# CurrentStabilizer_VER3.net
KiCad netlist of a schematic drawn in EAGLE
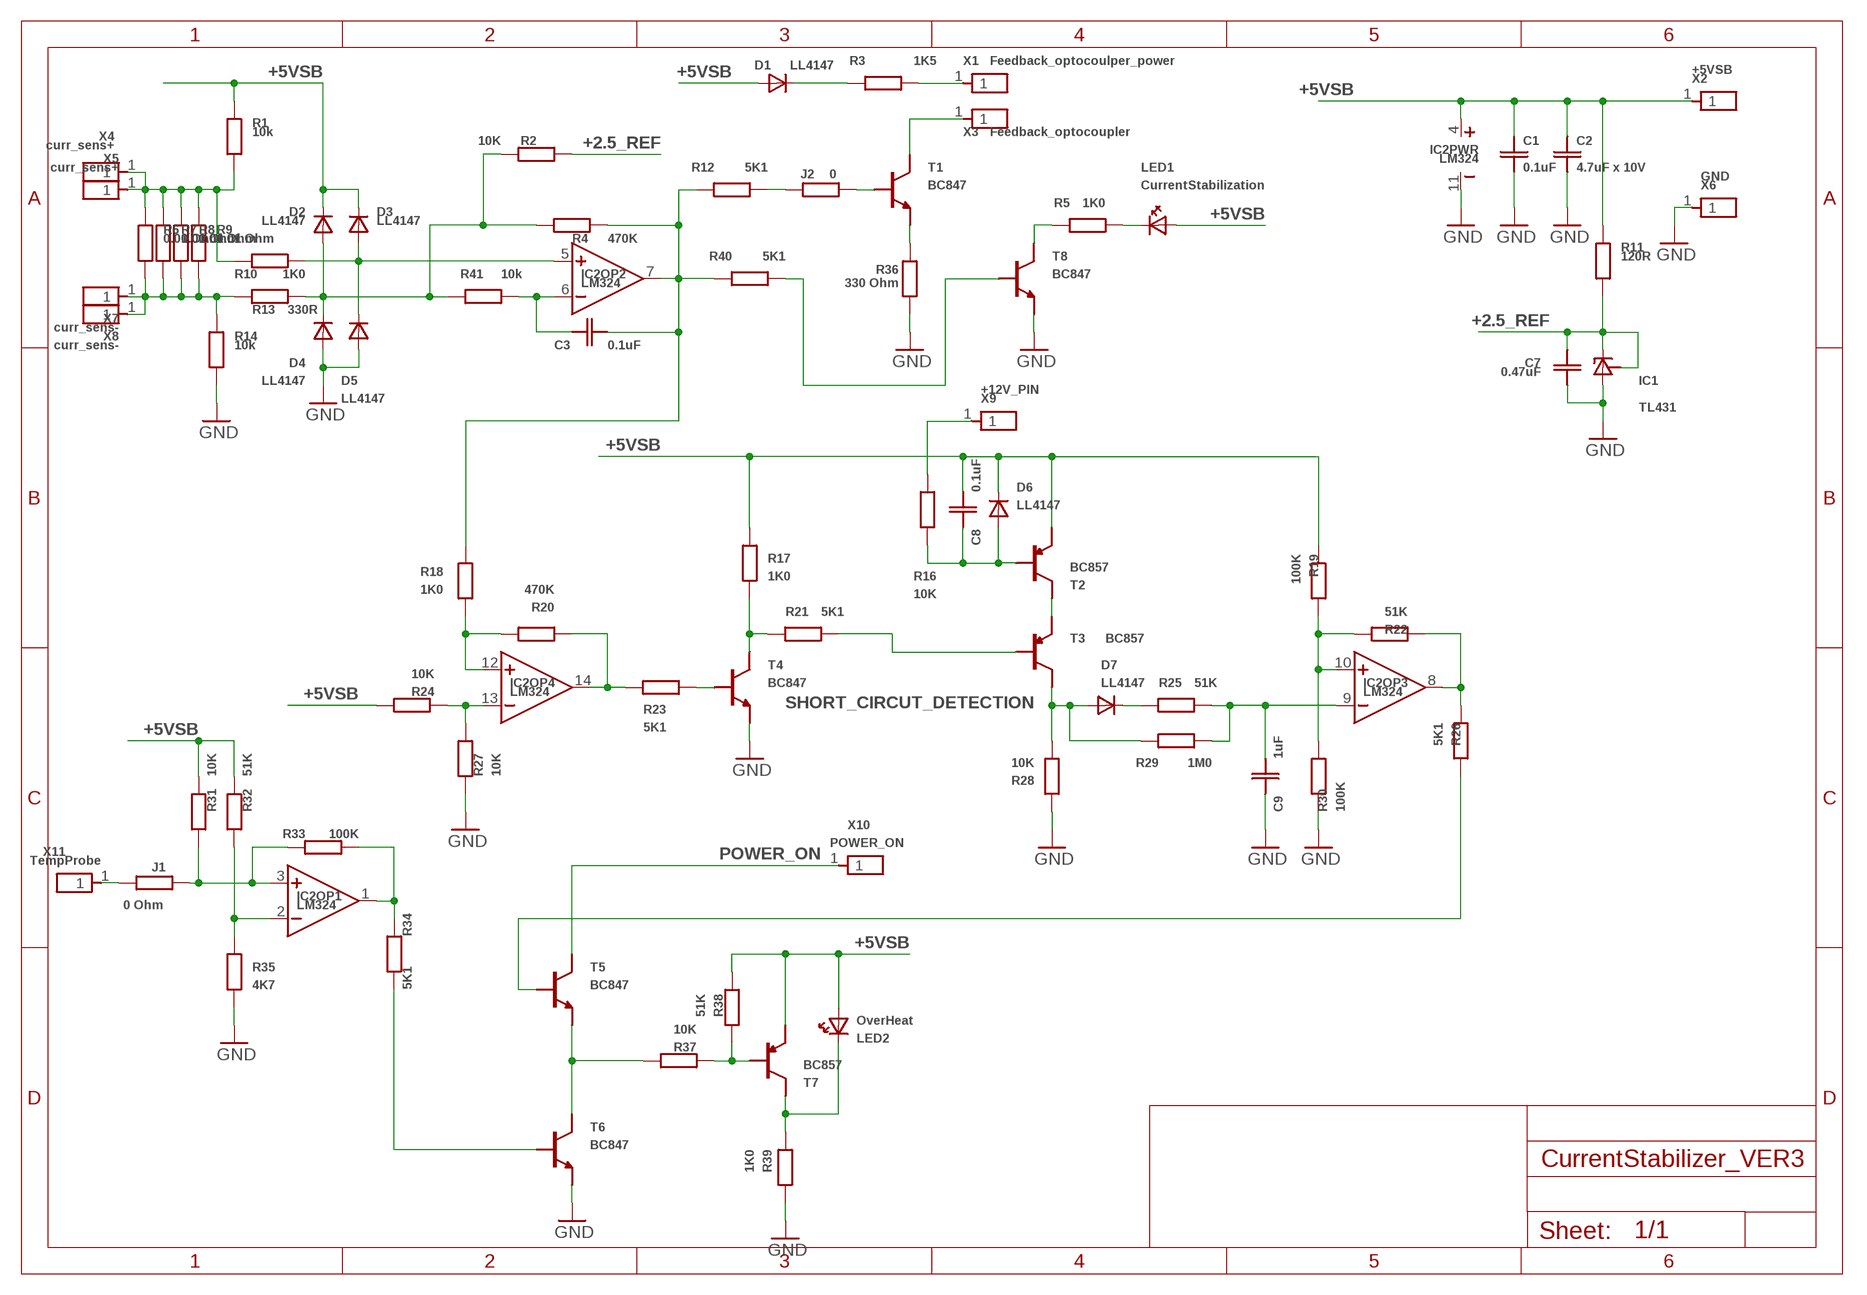
[diagram p0: schematic, sheet 1]

(export (version "E")
  (design (tool "Eeschema 10.0.6"))
  (components
    (comp (ref "C1")
      (value "0.1uF")
      (footprint "eagle-import:RSMD_0805")
      (libsource (lib "eagle-import") (part "CSMD_0805"))
    )
    (comp (ref "C2")
      (value "4.7uF x 10V")
      (footprint "eagle-import:RSMD_1206")
      (libsource (lib "eagle-import") (part "CSMD_1206"))
    )
    (comp (ref "C3")
      (value "0.1uF")
      (footprint "eagle-import:RSMD_0805")
      (libsource (lib "eagle-import") (part "CSMD_0805"))
    )
    (comp (ref "C7")
      (value "0.47uF")
      (footprint "eagle-import:RSMD_0805")
      (libsource (lib "eagle-import") (part "CSMD_0805"))
    )
    (comp (ref "C8")
      (value "0.1uF")
      (footprint "eagle-import:RSMD_0805")
      (libsource (lib "eagle-import") (part "CSMD_0805"))
    )
    (comp (ref "C9")
      (value "1uF")
      (footprint "eagle-import:RSMD_0805")
      (libsource (lib "eagle-import") (part "CSMD_0805"))
    )
    (comp (ref "D1")
      (value "LL4147")
      (footprint "eagle-import:SOD-80")
      (libsource (lib "eagle-import") (part "LL4147SOD-80"))
    )
    (comp (ref "D2")
      (value "LL4147")
      (footprint "eagle-import:SOD-80")
      (libsource (lib "eagle-import") (part "LL4147SOD-80"))
    )
    (comp (ref "D3")
      (value "LL4147")
      (footprint "eagle-import:SOD-80")
      (libsource (lib "eagle-import") (part "LL4147SOD-80"))
    )
    (comp (ref "D4")
      (value "LL4147")
      (footprint "eagle-import:SOD-80")
      (libsource (lib "eagle-import") (part "LL4147SOD-80"))
    )
    (comp (ref "D5")
      (value "LL4147")
      (footprint "eagle-import:SOD-80")
      (libsource (lib "eagle-import") (part "LL4147SOD-80"))
    )
    (comp (ref "D6")
      (value "LL4147")
      (footprint "eagle-import:SOD-80")
      (libsource (lib "eagle-import") (part "LL4147SOD-80"))
    )
    (comp (ref "D7")
      (value "LL4147")
      (footprint "eagle-import:SOD-80")
      (libsource (lib "eagle-import") (part "LL4147SOD-80"))
    )
    (comp (ref "IC1")
      (value "TL431")
      (footprint "eagle-import:SOT23")
      (libsource (lib "eagle-import") (part "TL431SOT23"))
    )
    (comp (ref "IC2")
      (value "LM324")
      (footprint "eagle-import:SOIC14")
      (libsource (lib "eagle-import") (part "LM324"))
    )
    (comp (ref "J1")
      (value "0 Ohm")
      (footprint "eagle-import:RSMD_0805")
      (libsource (lib "eagle-import") (part "RSMD_0805"))
    )
    (comp (ref "J2")
      (value "0")
      (footprint "eagle-import:RSMD_0805")
      (libsource (lib "eagle-import") (part "RSMD_0805"))
    )
    (comp (ref "LED1")
      (value "CurrentStabilization")
      (footprint "eagle-import:LED3MM")
      (libsource (lib "eagle-import") (part "LED3MM"))
    )
    (comp (ref "LED2")
      (value "OverHeat")
      (footprint "eagle-import:LED3MM")
      (libsource (lib "eagle-import") (part "LED3MM"))
    )
    (comp (ref "R1")
      (value "10k")
      (footprint "eagle-import:RSMD_0805")
      (libsource (lib "eagle-import") (part "RSMD_0805"))
    )
    (comp (ref "R2")
      (value "10K")
      (footprint "eagle-import:RSMD_0805")
      (libsource (lib "eagle-import") (part "RSMD_0805"))
    )
    (comp (ref "R3")
      (value "1K5")
      (footprint "eagle-import:RSMD_0805")
      (libsource (lib "eagle-import") (part "RSMD_0805"))
    )
    (comp (ref "R4")
      (value "470K")
      (footprint "eagle-import:RSMD_0805")
      (libsource (lib "eagle-import") (part "RSMD_0805"))
    )
    (comp (ref "R5")
      (value "1K0")
      (footprint "eagle-import:RSMD_0805")
      (libsource (lib "eagle-import") (part "RSMD_0805"))
    )
    (comp (ref "R6")
      (value "0.01 Ohm")
      (footprint "eagle-import:RSMD_2512")
      (libsource (lib "eagle-import") (part "RSMD_2512"))
    )
    (comp (ref "R7")
      (value "0.01 Ohm")
      (footprint "eagle-import:RSMD_2512")
      (libsource (lib "eagle-import") (part "RSMD_2512"))
    )
    (comp (ref "R8")
      (value "0.01 Ohm")
      (footprint "eagle-import:RSMD_2512")
      (libsource (lib "eagle-import") (part "RSMD_2512"))
    )
    (comp (ref "R9")
      (value "0.01 Ohm")
      (footprint "eagle-import:RSMD_2512")
      (libsource (lib "eagle-import") (part "RSMD_2512"))
    )
    (comp (ref "R10")
      (value "1K0")
      (footprint "eagle-import:RSMD_0805")
      (libsource (lib "eagle-import") (part "RSMD_0805"))
    )
    (comp (ref "R11")
      (value "120R")
      (footprint "eagle-import:RSMD_0805")
      (libsource (lib "eagle-import") (part "RSMD_0805"))
    )
    (comp (ref "R12")
      (value "5K1")
      (footprint "eagle-import:RSMD_0805")
      (libsource (lib "eagle-import") (part "RSMD_0805"))
    )
    (comp (ref "R13")
      (value "330R")
      (footprint "eagle-import:RSMD_0805")
      (libsource (lib "eagle-import") (part "RSMD_0805"))
    )
    (comp (ref "R14")
      (value "10k")
      (footprint "eagle-import:RSMD_0805")
      (libsource (lib "eagle-import") (part "RSMD_0805"))
    )
    (comp (ref "R16")
      (value "10K")
      (footprint "eagle-import:RSMD_0805")
      (libsource (lib "eagle-import") (part "RSMD_0805"))
    )
    (comp (ref "R17")
      (value "1K0")
      (footprint "eagle-import:RSMD_0805")
      (libsource (lib "eagle-import") (part "RSMD_0805"))
    )
    (comp (ref "R18")
      (value "1K0")
      (footprint "eagle-import:RSMD_0805")
      (libsource (lib "eagle-import") (part "RSMD_0805"))
    )
    (comp (ref "R19")
      (value "100K")
      (footprint "eagle-import:RSMD_1206_BIG_GAP")
      (libsource (lib "eagle-import") (part "RSMD_1206_BIG_GAP"))
    )
    (comp (ref "R20")
      (value "470K")
      (footprint "eagle-import:RSMD_0805")
      (libsource (lib "eagle-import") (part "RSMD_0805"))
    )
    (comp (ref "R21")
      (value "5K1")
      (footprint "eagle-import:RSMD_0805")
      (libsource (lib "eagle-import") (part "RSMD_0805"))
    )
    (comp (ref "R22")
      (value "51K")
      (footprint "eagle-import:RSMD_0805")
      (libsource (lib "eagle-import") (part "RSMD_0805"))
    )
    (comp (ref "R23")
      (value "5K1")
      (footprint "eagle-import:RSMD_1206_BIG_GAP")
      (libsource (lib "eagle-import") (part "RSMD_1206_BIG_GAP"))
    )
    (comp (ref "R24")
      (value "10K")
      (footprint "eagle-import:RSMD_0805")
      (libsource (lib "eagle-import") (part "RSMD_0805"))
    )
    (comp (ref "R25")
      (value "51K")
      (footprint "eagle-import:RSMD_0805")
      (libsource (lib "eagle-import") (part "RSMD_0805"))
    )
    (comp (ref "R26")
      (value "5K1")
      (footprint "eagle-import:RSMD_0805")
      (libsource (lib "eagle-import") (part "RSMD_0805"))
    )
    (comp (ref "R27")
      (value "10K")
      (footprint "eagle-import:RSMD_0805")
      (libsource (lib "eagle-import") (part "RSMD_0805"))
    )
    (comp (ref "R28")
      (value "10K")
      (footprint "eagle-import:RSMD_0805")
      (libsource (lib "eagle-import") (part "RSMD_0805"))
    )
    (comp (ref "R29")
      (value "1M0")
      (footprint "eagle-import:RSMD_0805")
      (libsource (lib "eagle-import") (part "RSMD_0805"))
    )
    (comp (ref "R30")
      (value "100K")
      (footprint "eagle-import:RSMD_0805")
      (libsource (lib "eagle-import") (part "RSMD_0805"))
    )
    (comp (ref "R31")
      (value "10K")
      (footprint "eagle-import:RSMD_0805")
      (libsource (lib "eagle-import") (part "RSMD_0805"))
    )
    (comp (ref "R32")
      (value "51K")
      (footprint "eagle-import:RSMD_0805")
      (libsource (lib "eagle-import") (part "RSMD_0805"))
    )
    (comp (ref "R33")
      (value "100K")
      (footprint "eagle-import:RSMD_0805")
      (libsource (lib "eagle-import") (part "RSMD_0805"))
    )
    (comp (ref "R34")
      (value "5K1")
      (footprint "eagle-import:RSMD_0805")
      (libsource (lib "eagle-import") (part "RSMD_0805"))
    )
    (comp (ref "R35")
      (value "4K7")
      (footprint "eagle-import:RSMD_0805")
      (libsource (lib "eagle-import") (part "RSMD_0805"))
    )
    (comp (ref "R36")
      (value "330 Ohm")
      (footprint "eagle-import:RSMD_0805")
      (libsource (lib "eagle-import") (part "RSMD_0805"))
    )
    (comp (ref "R37")
      (value "10K")
      (footprint "eagle-import:RSMD_1206_BIG_GAP")
      (libsource (lib "eagle-import") (part "RSMD_1206_BIG_GAP"))
    )
    (comp (ref "R38")
      (value "51K")
      (footprint "eagle-import:RSMD_0805")
      (libsource (lib "eagle-import") (part "RSMD_0805"))
    )
    (comp (ref "R39")
      (value "1K0")
      (footprint "eagle-import:RSMD_0805")
      (libsource (lib "eagle-import") (part "RSMD_0805"))
    )
    (comp (ref "R40")
      (value "5K1")
      (footprint "eagle-import:RSMD_0805")
      (libsource (lib "eagle-import") (part "RSMD_0805"))
    )
    (comp (ref "R41")
      (value "10k")
      (footprint "eagle-import:RSMD_0805")
      (libsource (lib "eagle-import") (part "RSMD_0805"))
    )
    (comp (ref "T1")
      (value "BC847")
      (footprint "eagle-import:SOT23_SMALL_PADS")
      (libsource (lib "eagle-import") (part "BC847SOT23_SMALL_PADS"))
    )
    (comp (ref "T2")
      (value "BC857")
      (footprint "eagle-import:SOT23_SMALL_PADS")
      (libsource (lib "eagle-import") (part "BC857SOT23_SMALL_PADS"))
    )
    (comp (ref "T3")
      (value "BC857")
      (footprint "eagle-import:SOT23_SMALL_PADS")
      (libsource (lib "eagle-import") (part "BC857SOT23_SMALL_PADS"))
    )
    (comp (ref "T4")
      (value "BC847")
      (footprint "eagle-import:SOT23_SMALL_PADS")
      (libsource (lib "eagle-import") (part "BC847SOT23_SMALL_PADS"))
    )
    (comp (ref "T5")
      (value "BC847")
      (footprint "eagle-import:SOT23_SMALL_PADS")
      (libsource (lib "eagle-import") (part "BC847SOT23_SMALL_PADS"))
    )
    (comp (ref "T6")
      (value "BC847")
      (footprint "eagle-import:SOT23_SMALL_PADS")
      (libsource (lib "eagle-import") (part "BC847SOT23_SMALL_PADS"))
    )
    (comp (ref "T7")
      (value "BC857")
      (footprint "eagle-import:SOT23_SMALL_PADS")
      (libsource (lib "eagle-import") (part "BC857SOT23_SMALL_PADS"))
    )
    (comp (ref "T8")
      (value "BC847")
      (footprint "eagle-import:SOT23_SMALL_PADS")
      (libsource (lib "eagle-import") (part "BC847SOT23_SMALL_PADS"))
    )
    (comp (ref "X1")
      (value "Feedback_optocoulper_power")
      (footprint "eagle-import:PIN1X1_2.54MM")
      (libsource (lib "eagle-import") (part "PIN1X12.54MM"))
    )
    (comp (ref "X2")
      (value "+5VSB")
      (footprint "eagle-import:PIN1X1_2.54MM")
      (libsource (lib "eagle-import") (part "PIN1X12.54MM"))
    )
    (comp (ref "X3")
      (value "Feedback_optocoupler")
      (footprint "eagle-import:PIN1X1_2.54MM")
      (libsource (lib "eagle-import") (part "PIN1X12.54MM"))
    )
    (comp (ref "X4")
      (value "curr_sens+")
      (footprint "eagle-import:PIN1X1_2.54MM")
      (libsource (lib "eagle-import") (part "PIN1X12.54MM"))
    )
    (comp (ref "X5")
      (value "curr_sens+")
      (footprint "eagle-import:PIN1X1_2.54MM")
      (libsource (lib "eagle-import") (part "PIN1X12.54MM"))
    )
    (comp (ref "X6")
      (value "GND")
      (footprint "eagle-import:PIN1X1_2.54MM")
      (libsource (lib "eagle-import") (part "PIN1X12.54MM"))
    )
    (comp (ref "X7")
      (value "curr_sens-")
      (footprint "eagle-import:PIN1X1_2.54MM")
      (libsource (lib "eagle-import") (part "PIN1X12.54MM"))
    )
    (comp (ref "X8")
      (value "curr_sens-")
      (footprint "eagle-import:PIN1X1_2.54MM")
      (libsource (lib "eagle-import") (part "PIN1X12.54MM"))
    )
    (comp (ref "X9")
      (value "+12V_PIN")
      (footprint "eagle-import:PIN1X1_2.54MM")
      (libsource (lib "eagle-import") (part "PIN1X12.54MM"))
    )
    (comp (ref "X10")
      (value "POWER_ON")
      (footprint "eagle-import:PIN1X1_2.54MM")
      (libsource (lib "eagle-import") (part "PIN1X12.54MM"))
    )
    (comp (ref "X11")
      (value "TempProbe")
      (footprint "eagle-import:PIN1X1_2.54MM")
      (libsource (lib "eagle-import") (part "PIN1X12.54MM"))
    )
  )
  (nets
    (net (code "1") (name "/+2.5_REF") (class "Default")
      (node (ref "C7") (pin "PAD_1") (pinfunction "PIN1_PAD_1") (pintype "bidirectional"))
      (node (ref "IC1") (pin "1") (pinfunction "CATHODE_1") (pintype "passive"))
      (node (ref "IC1") (pin "2") (pinfunction "REFERENCE_2") (pintype "passive"))
      (node (ref "R11") (pin "PAD_0") (pinfunction "PIN0_PAD_0") (pintype "passive"))
      (node (ref "R2") (pin "PAD_0") (pinfunction "PIN0_PAD_0") (pintype "passive"))
    )
    (net (code "2") (name "/+5VSB") (class "Default")
      (node (ref "C1") (pin "PAD_1") (pinfunction "PIN1_PAD_1") (pintype "bidirectional"))
      (node (ref "C2") (pin "PAD_1") (pinfunction "PIN1_PAD_1") (pintype "bidirectional"))
      (node (ref "C8") (pin "PAD_0") (pinfunction "PIN0_PAD_0") (pintype "bidirectional"))
      (node (ref "D1") (pin "ANODE") (pinfunction "ANODE_ANODE") (pintype "passive"))
      (node (ref "D2") (pin "CATHODE") (pinfunction "CATHODE_CATHODE") (pintype "passive"))
      (node (ref "D3") (pin "CATHODE") (pinfunction "CATHODE_CATHODE") (pintype "passive"))
      (node (ref "D6") (pin "CATHODE") (pinfunction "CATHODE_CATHODE") (pintype "passive"))
      (node (ref "IC2") (pin "4") (pinfunction "VCC_4") (pintype "power_in"))
      (node (ref "LED1") (pin "ANODE") (pinfunction "ANODE_ANODE") (pintype "passive"))
      (node (ref "LED2") (pin "ANODE") (pinfunction "ANODE_ANODE") (pintype "passive"))
      (node (ref "R1") (pin "PAD_1") (pinfunction "PIN1_PAD_1") (pintype "passive"))
      (node (ref "R11") (pin "PAD_1") (pinfunction "PIN1_PAD_1") (pintype "passive"))
      (node (ref "R17") (pin "PAD_0") (pinfunction "PIN0_PAD_0") (pintype "passive"))
      (node (ref "R19") (pin "PAD_0") (pinfunction "PIN0_PAD_0") (pintype "passive"))
      (node (ref "R24") (pin "PAD_1") (pinfunction "PIN1_PAD_1") (pintype "passive"))
      (node (ref "R31") (pin "PAD_1") (pinfunction "PIN1_PAD_1") (pintype "passive"))
      (node (ref "R32") (pin "PAD_1") (pinfunction "PIN1_PAD_1") (pintype "passive"))
      (node (ref "R38") (pin "PAD_0") (pinfunction "PIN0_PAD_0") (pintype "passive"))
      (node (ref "T2") (pin "2") (pinfunction "E_2") (pintype "bidirectional"))
      (node (ref "T7") (pin "2") (pinfunction "E_2") (pintype "bidirectional"))
      (node (ref "X2") (pin "1") (pinfunction "1_1") (pintype "bidirectional"))
    )
    (net (code "3") (name "/POWER_ON") (class "Default")
      (node (ref "T5") (pin "3") (pinfunction "C_3") (pintype "bidirectional"))
      (node (ref "X10") (pin "1") (pinfunction "1_1") (pintype "bidirectional"))
    )
    (net (code "4") (name "/SHORT_CIRCUT_DETECTION") (class "Default")
      (node (ref "D7") (pin "ANODE") (pinfunction "ANODE_ANODE") (pintype "passive"))
      (node (ref "R28") (pin "PAD_0") (pinfunction "PIN0_PAD_0") (pintype "passive"))
      (node (ref "R29") (pin "PAD_1") (pinfunction "PIN1_PAD_1") (pintype "passive"))
      (node (ref "T3") (pin "3") (pinfunction "C_3") (pintype "bidirectional"))
    )
    (net (code "5") (name "GND") (class "Default")
      (node (ref "C1") (pin "PAD_0") (pinfunction "PIN0_PAD_0") (pintype "bidirectional"))
      (node (ref "C2") (pin "PAD_0") (pinfunction "PIN0_PAD_0") (pintype "bidirectional"))
      (node (ref "C7") (pin "PAD_0") (pinfunction "PIN0_PAD_0") (pintype "bidirectional"))
      (node (ref "C9") (pin "PAD_1") (pinfunction "PIN1_PAD_1") (pintype "bidirectional"))
      (node (ref "D4") (pin "ANODE") (pinfunction "ANODE_ANODE") (pintype "passive"))
      (node (ref "D5") (pin "ANODE") (pinfunction "ANODE_ANODE") (pintype "passive"))
      (node (ref "IC1") (pin "3") (pinfunction "ANODE_3") (pintype "passive"))
      (node (ref "IC2") (pin "11") (pinfunction "GND_11") (pintype "power_in"))
      (node (ref "R14") (pin "PAD_0") (pinfunction "PIN0_PAD_0") (pintype "passive"))
      (node (ref "R27") (pin "PAD_0") (pinfunction "PIN0_PAD_0") (pintype "passive"))
      (node (ref "R28") (pin "PAD_1") (pinfunction "PIN1_PAD_1") (pintype "passive"))
      (node (ref "R30") (pin "PAD_0") (pinfunction "PIN0_PAD_0") (pintype "passive"))
      (node (ref "R35") (pin "PAD_0") (pinfunction "PIN0_PAD_0") (pintype "passive"))
      (node (ref "R36") (pin "PAD_0") (pinfunction "PIN0_PAD_0") (pintype "passive"))
      (node (ref "R39") (pin "PAD_1") (pinfunction "PIN1_PAD_1") (pintype "passive"))
      (node (ref "T4") (pin "2") (pinfunction "E_2") (pintype "bidirectional"))
      (node (ref "T6") (pin "2") (pinfunction "E_2") (pintype "bidirectional"))
      (node (ref "T8") (pin "2") (pinfunction "E_2") (pintype "bidirectional"))
      (node (ref "X6") (pin "1") (pinfunction "1_1") (pintype "bidirectional"))
    )
    (net (code "6") (name "Net-(C3-PIN0)") (class "Default")
      (node (ref "C3") (pin "PAD_0") (pinfunction "PIN0_PAD_0") (pintype "bidirectional"))
      (node (ref "IC2") (pin "7") (pinfunction "OUT_7") (pintype "output"))
      (node (ref "R12") (pin "PAD_1") (pinfunction "PIN1_PAD_1") (pintype "passive"))
      (node (ref "R18") (pin "PAD_1") (pinfunction "PIN1_PAD_1") (pintype "passive"))
      (node (ref "R4") (pin "PAD_1") (pinfunction "PIN1_PAD_1") (pintype "passive"))
      (node (ref "R40") (pin "PAD_1") (pinfunction "PIN1_PAD_1") (pintype "passive"))
    )
    (net (code "7") (name "Net-(C3-PIN1)") (class "Default")
      (node (ref "C3") (pin "PAD_1") (pinfunction "PIN1_PAD_1") (pintype "bidirectional"))
      (node (ref "IC2") (pin "6") (pinfunction "IN-_6") (pintype "input"))
      (node (ref "R41") (pin "PAD_0") (pinfunction "PIN0_PAD_0") (pintype "passive"))
    )
    (net (code "8") (name "Net-(C8-PIN1)") (class "Default")
      (node (ref "C8") (pin "PAD_1") (pinfunction "PIN1_PAD_1") (pintype "bidirectional"))
      (node (ref "D6") (pin "ANODE") (pinfunction "ANODE_ANODE") (pintype "passive"))
      (node (ref "R16") (pin "PAD_1") (pinfunction "PIN1_PAD_1") (pintype "passive"))
      (node (ref "T2") (pin "1") (pinfunction "B_1") (pintype "bidirectional"))
    )
    (net (code "9") (name "Net-(C9-PIN0)") (class "Default")
      (node (ref "C9") (pin "PAD_0") (pinfunction "PIN0_PAD_0") (pintype "bidirectional"))
      (node (ref "IC2") (pin "9") (pinfunction "IN-_9") (pintype "input"))
      (node (ref "R25") (pin "PAD_1") (pinfunction "PIN1_PAD_1") (pintype "passive"))
      (node (ref "R29") (pin "PAD_0") (pinfunction "PIN0_PAD_0") (pintype "passive"))
    )
    (net (code "10") (name "Net-(IC2A-IN+)") (class "Default")
      (node (ref "IC2") (pin "3") (pinfunction "IN+_3") (pintype "input"))
      (node (ref "J1") (pin "PAD_0") (pinfunction "PIN0_PAD_0") (pintype "passive"))
      (node (ref "R31") (pin "PAD_0") (pinfunction "PIN0_PAD_0") (pintype "passive"))
      (node (ref "R33") (pin "PAD_1") (pinfunction "PIN1_PAD_1") (pintype "passive"))
    )
    (net (code "11") (name "Net-(IC2A-IN-)") (class "Default")
      (node (ref "IC2") (pin "2") (pinfunction "IN-_2") (pintype "input"))
      (node (ref "R32") (pin "PAD_0") (pinfunction "PIN0_PAD_0") (pintype "passive"))
      (node (ref "R35") (pin "PAD_1") (pinfunction "PIN1_PAD_1") (pintype "passive"))
    )
    (net (code "12") (name "Net-(IC2A-OUT)") (class "Default")
      (node (ref "IC2") (pin "1") (pinfunction "OUT_1") (pintype "output"))
      (node (ref "R33") (pin "PAD_0") (pinfunction "PIN0_PAD_0") (pintype "passive"))
      (node (ref "R34") (pin "PAD_1") (pinfunction "PIN1_PAD_1") (pintype "passive"))
    )
    (net (code "13") (name "Net-(IC2B-IN+)") (class "Default")
      (node (ref "D3") (pin "ANODE") (pinfunction "ANODE_ANODE") (pintype "passive"))
      (node (ref "D5") (pin "CATHODE") (pinfunction "CATHODE_CATHODE") (pintype "passive"))
      (node (ref "IC2") (pin "5") (pinfunction "IN+_5") (pintype "input"))
      (node (ref "R10") (pin "PAD_1") (pinfunction "PIN1_PAD_1") (pintype "passive"))
    )
    (net (code "14") (name "Net-(IC2C-IN+)") (class "Default")
      (node (ref "IC2") (pin "10") (pinfunction "IN+_10") (pintype "input"))
      (node (ref "R19") (pin "PAD_1") (pinfunction "PIN1_PAD_1") (pintype "passive"))
      (node (ref "R22") (pin "PAD_1") (pinfunction "PIN1_PAD_1") (pintype "passive"))
      (node (ref "R30") (pin "PAD_1") (pinfunction "PIN1_PAD_1") (pintype "passive"))
    )
    (net (code "15") (name "Net-(IC2C-OUT)") (class "Default")
      (node (ref "IC2") (pin "8") (pinfunction "OUT_8") (pintype "output"))
      (node (ref "R22") (pin "PAD_0") (pinfunction "PIN0_PAD_0") (pintype "passive"))
      (node (ref "R26") (pin "PAD_0") (pinfunction "PIN0_PAD_0") (pintype "passive"))
    )
    (net (code "16") (name "Net-(IC2D-IN+)") (class "Default")
      (node (ref "IC2") (pin "12") (pinfunction "IN+_12") (pintype "input"))
      (node (ref "R18") (pin "PAD_0") (pinfunction "PIN0_PAD_0") (pintype "passive"))
      (node (ref "R20") (pin "PAD_0") (pinfunction "PIN0_PAD_0") (pintype "passive"))
    )
    (net (code "17") (name "Net-(IC2D-IN-)") (class "Default")
      (node (ref "IC2") (pin "13") (pinfunction "IN-_13") (pintype "input"))
      (node (ref "R24") (pin "PAD_0") (pinfunction "PIN0_PAD_0") (pintype "passive"))
      (node (ref "R27") (pin "PAD_1") (pinfunction "PIN1_PAD_1") (pintype "passive"))
    )
    (net (code "18") (name "Net-(IC2D-OUT)") (class "Default")
      (node (ref "IC2") (pin "14") (pinfunction "OUT_14") (pintype "output"))
      (node (ref "R20") (pin "PAD_1") (pinfunction "PIN1_PAD_1") (pintype "passive"))
      (node (ref "R23") (pin "PAD_1") (pinfunction "PIN1_PAD_1") (pintype "passive"))
    )
    (net (code "19") (name "Net-(J1-PIN1)") (class "Default")
      (node (ref "J1") (pin "PAD_1") (pinfunction "PIN1_PAD_1") (pintype "passive"))
      (node (ref "X11") (pin "1") (pinfunction "1_1") (pintype "bidirectional"))
    )
    (net (code "20") (name "Net-(J2-PIN0)") (class "Default")
      (node (ref "J2") (pin "PAD_0") (pinfunction "PIN0_PAD_0") (pintype "passive"))
      (node (ref "T1") (pin "1") (pinfunction "B_1") (pintype "bidirectional"))
    )
    (net (code "21") (name "Net-(J2-PIN1)") (class "Default")
      (node (ref "J2") (pin "PAD_1") (pinfunction "PIN1_PAD_1") (pintype "passive"))
      (node (ref "R12") (pin "PAD_0") (pinfunction "PIN0_PAD_0") (pintype "passive"))
    )
    (net (code "22") (name "Net-(R1-PIN0)") (class "Default")
      (node (ref "R1") (pin "PAD_0") (pinfunction "PIN0_PAD_0") (pintype "passive"))
      (node (ref "R10") (pin "PAD_0") (pinfunction "PIN0_PAD_0") (pintype "passive"))
      (node (ref "R6") (pin "PAD1") (pinfunction "PIN1_PAD1") (pintype "passive"))
      (node (ref "R7") (pin "PAD1") (pinfunction "PIN1_PAD1") (pintype "passive"))
      (node (ref "R8") (pin "PAD1") (pinfunction "PIN1_PAD1") (pintype "passive"))
      (node (ref "R9") (pin "PAD1") (pinfunction "PIN1_PAD1") (pintype "passive"))
      (node (ref "X4") (pin "1") (pinfunction "1_1") (pintype "bidirectional"))
      (node (ref "X5") (pin "1") (pinfunction "1_1") (pintype "bidirectional"))
    )
    (net (code "23") (name "Net-(R3-PIN0)") (class "Default")
      (node (ref "R3") (pin "PAD_0") (pinfunction "PIN0_PAD_0") (pintype "passive"))
      (node (ref "X1") (pin "1") (pinfunction "1_1") (pintype "bidirectional"))
    )
    (net (code "24") (name "Net-(R3-PIN1)") (class "Default")
      (node (ref "D1") (pin "CATHODE") (pinfunction "CATHODE_CATHODE") (pintype "passive"))
      (node (ref "R3") (pin "PAD_1") (pinfunction "PIN1_PAD_1") (pintype "passive"))
    )
    (net (code "25") (name "Net-(R5-PIN0)") (class "Default")
      (node (ref "LED1") (pin "CATHODE") (pinfunction "CATHODE_CATHODE") (pintype "passive"))
      (node (ref "R5") (pin "PAD_0") (pinfunction "PIN0_PAD_0") (pintype "passive"))
    )
    (net (code "26") (name "Net-(R5-PIN1)") (class "Default")
      (node (ref "R5") (pin "PAD_1") (pinfunction "PIN1_PAD_1") (pintype "passive"))
      (node (ref "T8") (pin "3") (pinfunction "C_3") (pintype "bidirectional"))
    )
    (net (code "27") (name "Net-(R13-PIN0)") (class "Default")
      (node (ref "R13") (pin "PAD_0") (pinfunction "PIN0_PAD_0") (pintype "passive"))
      (node (ref "R14") (pin "PAD_1") (pinfunction "PIN1_PAD_1") (pintype "passive"))
      (node (ref "R6") (pin "PAD0") (pinfunction "PIN0_PAD0") (pintype "passive"))
      (node (ref "R7") (pin "PAD0") (pinfunction "PIN0_PAD0") (pintype "passive"))
      (node (ref "R8") (pin "PAD0") (pinfunction "PIN0_PAD0") (pintype "passive"))
      (node (ref "R9") (pin "PAD0") (pinfunction "PIN0_PAD0") (pintype "passive"))
      (node (ref "X7") (pin "1") (pinfunction "1_1") (pintype "bidirectional"))
      (node (ref "X8") (pin "1") (pinfunction "1_1") (pintype "bidirectional"))
    )
    (net (code "28") (name "Net-(R13-PIN1)") (class "Default")
      (node (ref "D2") (pin "ANODE") (pinfunction "ANODE_ANODE") (pintype "passive"))
      (node (ref "D4") (pin "CATHODE") (pinfunction "CATHODE_CATHODE") (pintype "passive"))
      (node (ref "R13") (pin "PAD_1") (pinfunction "PIN1_PAD_1") (pintype "passive"))
      (node (ref "R2") (pin "PAD_1") (pinfunction "PIN1_PAD_1") (pintype "passive"))
      (node (ref "R4") (pin "PAD_0") (pinfunction "PIN0_PAD_0") (pintype "passive"))
      (node (ref "R41") (pin "PAD_1") (pinfunction "PIN1_PAD_1") (pintype "passive"))
    )
    (net (code "29") (name "Net-(R16-PIN0)") (class "Default")
      (node (ref "R16") (pin "PAD_0") (pinfunction "PIN0_PAD_0") (pintype "passive"))
      (node (ref "X9") (pin "1") (pinfunction "1_1") (pintype "bidirectional"))
    )
    (net (code "30") (name "Net-(R17-PIN1)") (class "Default")
      (node (ref "R17") (pin "PAD_1") (pinfunction "PIN1_PAD_1") (pintype "passive"))
      (node (ref "R21") (pin "PAD_0") (pinfunction "PIN0_PAD_0") (pintype "passive"))
      (node (ref "T4") (pin "3") (pinfunction "C_3") (pintype "bidirectional"))
    )
    (net (code "31") (name "Net-(R21-PIN1)") (class "Default")
      (node (ref "R21") (pin "PAD_1") (pinfunction "PIN1_PAD_1") (pintype "passive"))
      (node (ref "T3") (pin "1") (pinfunction "B_1") (pintype "bidirectional"))
    )
    (net (code "32") (name "Net-(R23-PIN0)") (class "Default")
      (node (ref "R23") (pin "PAD_0") (pinfunction "PIN0_PAD_0") (pintype "passive"))
      (node (ref "T4") (pin "1") (pinfunction "B_1") (pintype "bidirectional"))
    )
    (net (code "33") (name "Net-(R25-PIN0)") (class "Default")
      (node (ref "D7") (pin "CATHODE") (pinfunction "CATHODE_CATHODE") (pintype "passive"))
      (node (ref "R25") (pin "PAD_0") (pinfunction "PIN0_PAD_0") (pintype "passive"))
    )
    (net (code "34") (name "Net-(R26-PIN1)") (class "Default")
      (node (ref "R26") (pin "PAD_1") (pinfunction "PIN1_PAD_1") (pintype "passive"))
      (node (ref "T5") (pin "1") (pinfunction "B_1") (pintype "bidirectional"))
    )
    (net (code "35") (name "Net-(R34-PIN0)") (class "Default")
      (node (ref "R34") (pin "PAD_0") (pinfunction "PIN0_PAD_0") (pintype "passive"))
      (node (ref "T6") (pin "1") (pinfunction "B_1") (pintype "bidirectional"))
    )
    (net (code "36") (name "Net-(R36-PIN1)") (class "Default")
      (node (ref "R36") (pin "PAD_1") (pinfunction "PIN1_PAD_1") (pintype "passive"))
      (node (ref "T1") (pin "2") (pinfunction "E_2") (pintype "bidirectional"))
    )
    (net (code "37") (name "Net-(R37-PIN0)") (class "Default")
      (node (ref "R37") (pin "PAD_0") (pinfunction "PIN0_PAD_0") (pintype "passive"))
      (node (ref "R38") (pin "PAD_1") (pinfunction "PIN1_PAD_1") (pintype "passive"))
      (node (ref "T7") (pin "1") (pinfunction "B_1") (pintype "bidirectional"))
    )
    (net (code "38") (name "Net-(R37-PIN1)") (class "Default")
      (node (ref "R37") (pin "PAD_1") (pinfunction "PIN1_PAD_1") (pintype "passive"))
      (node (ref "T5") (pin "2") (pinfunction "E_2") (pintype "bidirectional"))
      (node (ref "T6") (pin "3") (pinfunction "C_3") (pintype "bidirectional"))
    )
    (net (code "39") (name "Net-(R39-PIN0)") (class "Default")
      (node (ref "LED2") (pin "CATHODE") (pinfunction "CATHODE_CATHODE") (pintype "passive"))
      (node (ref "R39") (pin "PAD_0") (pinfunction "PIN0_PAD_0") (pintype "passive"))
      (node (ref "T7") (pin "3") (pinfunction "C_3") (pintype "bidirectional"))
    )
    (net (code "40") (name "Net-(R40-PIN0)") (class "Default")
      (node (ref "R40") (pin "PAD_0") (pinfunction "PIN0_PAD_0") (pintype "passive"))
      (node (ref "T8") (pin "1") (pinfunction "B_1") (pintype "bidirectional"))
    )
    (net (code "41") (name "Net-(T1-C)") (class "Default")
      (node (ref "T1") (pin "3") (pinfunction "C_3") (pintype "bidirectional"))
      (node (ref "X3") (pin "1") (pinfunction "1_1") (pintype "bidirectional"))
    )
    (net (code "42") (name "Net-(T2-C)") (class "Default")
      (node (ref "T2") (pin "3") (pinfunction "C_3") (pintype "bidirectional"))
      (node (ref "T3") (pin "2") (pinfunction "E_2") (pintype "bidirectional"))
    )
  )
)
